# R7FA4M3AF3CFB.net
KiCad netlist of a schematic drawn in Altium Designer
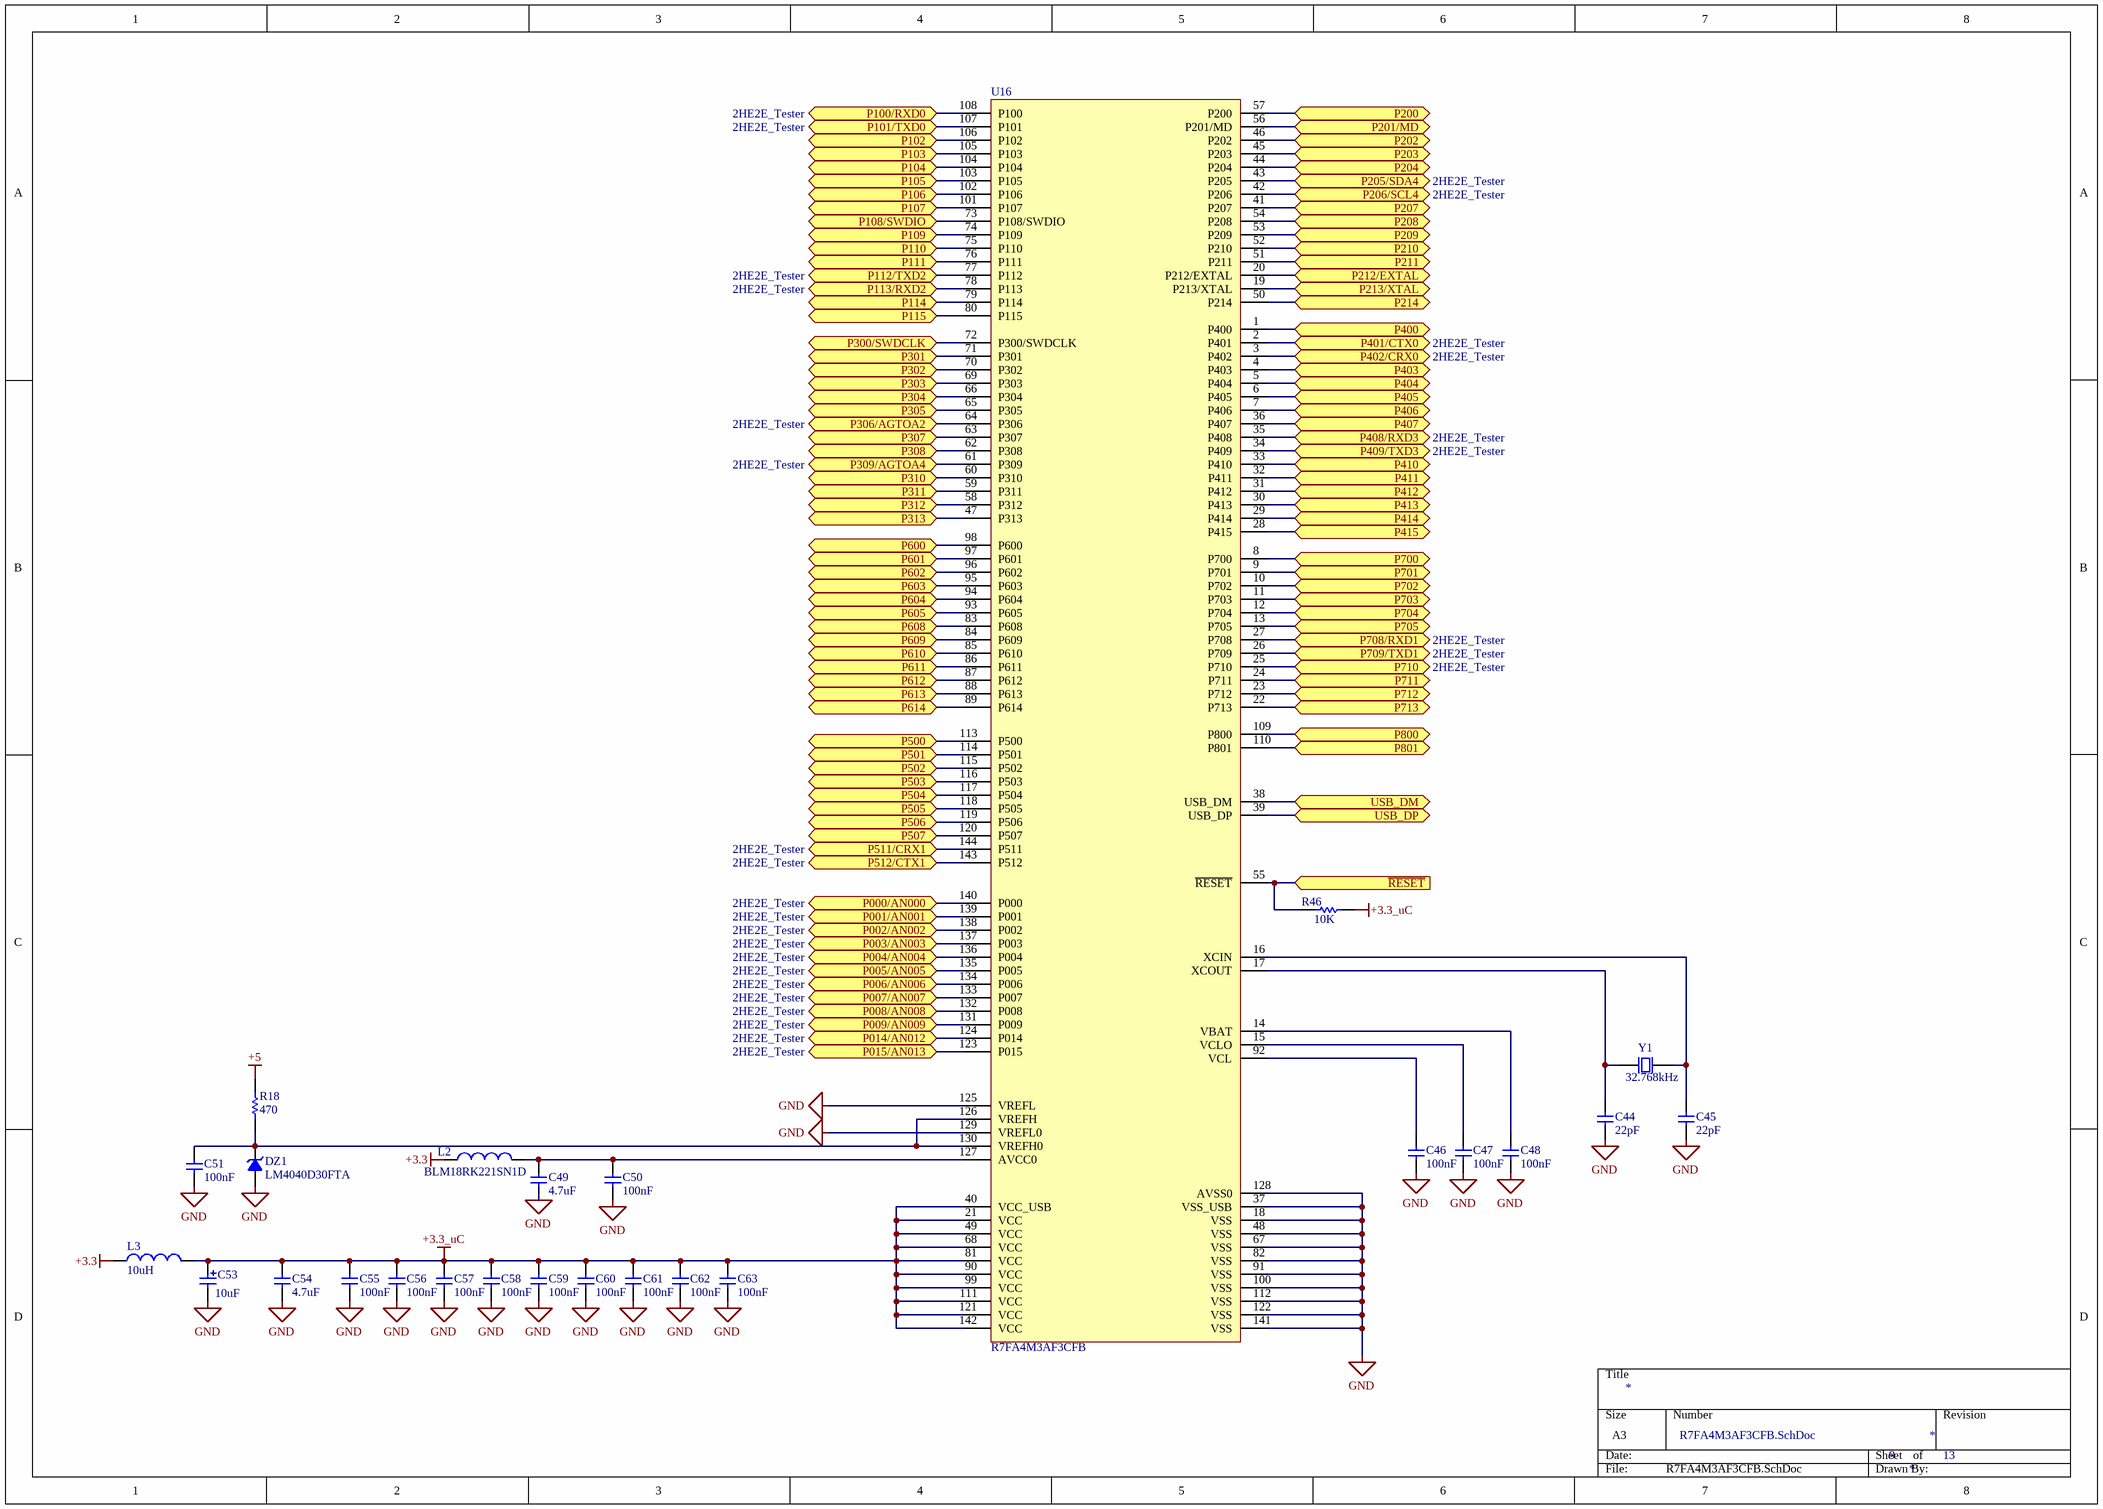
[diagram p0: R7FA4M3AF3CFB.SchDoc]

(export (version "E")
  (design (tool "Eeschema 10.0.6"))
  (components
    (comp (ref "C44")
      (value "22pF")
      (footprint "0603M-C")
      (description "Ceramic Capacitor")
      (fields (field (name "Comment") "Cap Ceramic"))
      (libsource (lib "Plume") (part "Cap Ceramic"))
    )
    (comp (ref "C45")
      (value "22pF")
      (footprint "0603M-C")
      (description "Ceramic Capacitor")
      (fields (field (name "Comment") "Cap Ceramic"))
      (libsource (lib "Plume") (part "Cap Ceramic"))
    )
    (comp (ref "C46")
      (value "100nF")
      (footprint "0603M-C")
      (description "Ceramic Capacitor 25V")
      (fields (field (name "Comment") "Cap Ceramic"))
      (libsource (lib "Plume") (part "Cap Ceramic"))
    )
    (comp (ref "C47")
      (value "100nF")
      (footprint "0603M-C")
      (description "Ceramic Capacitor 25V")
      (fields (field (name "Comment") "Cap Ceramic"))
      (libsource (lib "Plume") (part "Cap Ceramic"))
    )
    (comp (ref "C48")
      (value "100nF")
      (footprint "0603M-C")
      (description "Ceramic Capacitor 25V")
      (fields (field (name "Comment") "Cap Ceramic"))
      (libsource (lib "Plume") (part "Cap Ceramic"))
    )
    (comp (ref "C49")
      (value "4.7uF")
      (footprint "0603M-C")
      (description "Ceramic Capacitor 6.3V")
      (fields (field (name "Comment") "Cap Ceramic"))
      (libsource (lib "Plume") (part "Cap Ceramic"))
    )
    (comp (ref "C50")
      (value "100nF")
      (footprint "0603M-C")
      (description "Ceramic Capacitor 25V")
      (fields (field (name "Comment") "Cap Ceramic"))
      (libsource (lib "Plume") (part "Cap Ceramic"))
    )
    (comp (ref "C51")
      (value "100nF")
      (footprint "0603M-C")
      (description "Ceramic Capacitor 25V")
      (fields (field (name "Comment") "Cap Ceramic"))
      (libsource (lib "Plume") (part "Cap Ceramic"))
    )
    (comp (ref "C53")
      (value "10uF")
      (footprint "Cap CASE A")
      (description "Capacitor tantalio 10V")
      (fields (field (name "Comment") "Cap Tantalio"))
      (libsource (lib "Plume") (part "Cap Tantalio"))
    )
    (comp (ref "C54")
      (value "4.7uF")
      (footprint "0603M-C")
      (description "Ceramic Capacitor 6.3V")
      (fields (field (name "Comment") "Cap Ceramic"))
      (libsource (lib "Plume") (part "Cap Ceramic"))
    )
    (comp (ref "C55")
      (value "100nF")
      (footprint "0603M-C")
      (description "Ceramic Capacitor 25V")
      (fields (field (name "Comment") "Cap Ceramic"))
      (libsource (lib "Plume") (part "Cap Ceramic"))
    )
    (comp (ref "C56")
      (value "100nF")
      (footprint "0603M-C")
      (description "Ceramic Capacitor 25V")
      (fields (field (name "Comment") "Cap Ceramic"))
      (libsource (lib "Plume") (part "Cap Ceramic"))
    )
    (comp (ref "C57")
      (value "100nF")
      (footprint "0603M-C")
      (description "Ceramic Capacitor 25V")
      (fields (field (name "Comment") "Cap Ceramic"))
      (libsource (lib "Plume") (part "Cap Ceramic"))
    )
    (comp (ref "C58")
      (value "100nF")
      (footprint "0603M-C")
      (description "Ceramic Capacitor 25V")
      (fields (field (name "Comment") "Cap Ceramic"))
      (libsource (lib "Plume") (part "Cap Ceramic"))
    )
    (comp (ref "C59")
      (value "100nF")
      (footprint "0603M-C")
      (description "Ceramic Capacitor 25V")
      (fields (field (name "Comment") "Cap Ceramic"))
      (libsource (lib "Plume") (part "Cap Ceramic"))
    )
    (comp (ref "C60")
      (value "100nF")
      (footprint "0603M-C")
      (description "Ceramic Capacitor 25V")
      (fields (field (name "Comment") "Cap Ceramic"))
      (libsource (lib "Plume") (part "Cap Ceramic"))
    )
    (comp (ref "C61")
      (value "100nF")
      (footprint "0603M-C")
      (description "Ceramic Capacitor 25V")
      (fields (field (name "Comment") "Cap Ceramic"))
      (libsource (lib "Plume") (part "Cap Ceramic"))
    )
    (comp (ref "C62")
      (value "100nF")
      (footprint "0603M-C")
      (description "Ceramic Capacitor 25V")
      (fields (field (name "Comment") "Cap Ceramic"))
      (libsource (lib "Plume") (part "Cap Ceramic"))
    )
    (comp (ref "C63")
      (value "100nF")
      (footprint "0603M-C")
      (description "Ceramic Capacitor 25V")
      (fields (field (name "Comment") "Cap Ceramic"))
      (libsource (lib "Plume") (part "Cap Ceramic"))
    )
    (comp (ref "DZ1")
      (value "LM4040D30FTA")
      (footprint "SOT23 ZR4040")
      (description "Reference 3V")
      (libsource (lib "Plume") (part "Diodo Zener"))
    )
    (comp (ref "L2")
      (value "BLM18RK221SN1D")
      (footprint "0603M")
      (description "Ferrite Bead")
      (libsource (lib "Plume") (part "Induttanza"))
    )
    (comp (ref "L3")
      (value "10uH")
      (footprint "1210ML")
      (description "WE 744032100")
      (fields (field (name "Comment") "Induttanza"))
      (libsource (lib "Plume") (part "Induttanza"))
    )
    (comp (ref "R18")
      (value "470")
      (footprint "0603M")
      (description "Resistor")
      (libsource (lib "Plume") (part "Resistor"))
    )
    (comp (ref "R46")
      (value "10K")
      (footprint "0603M")
      (description "Resistor")
      (libsource (lib "Plume") (part "Resistor"))
    )
    (comp (ref "U16")
      (value "R7FA4M3AF3CFB")
      (footprint "TQFP50P2200X2200X170-144N")
      (description "RA4M3 100 MHz Arm Cortex-M33 core 144 pin")
      (libsource (lib "Plume") (part "R7FA4M3Ax3CFB"))
    )
    (comp (ref "Y1")
      (value "32.768kHz")
      (footprint "WE-XTAL_CFPX-217")
      (description "WE-XTAL  830108488401- Watch Crystals  32.768kHz ±20ppm 12.5pF")
      (libsource (lib "Plume") (part "Quarzo"))
    )
  )
  (nets
    (net (code "1") (name "+3.3") (class "Default")
      (node (ref "L2") (pin "1") (pinfunction "1_1") (pintype "passive"))
      (node (ref "L3") (pin "1") (pinfunction "1_1") (pintype "passive"))
    )
    (net (code "2") (name "+3.3_uC") (class "Default")
      (node (ref "C53") (pin "1") (pinfunction "1_1") (pintype "passive"))
      (node (ref "C54") (pin "2") (pinfunction "2_2") (pintype "passive"))
      (node (ref "C55") (pin "2") (pinfunction "2_2") (pintype "passive"))
      (node (ref "C56") (pin "2") (pinfunction "2_2") (pintype "passive"))
      (node (ref "C57") (pin "2") (pinfunction "2_2") (pintype "passive"))
      (node (ref "C58") (pin "2") (pinfunction "2_2") (pintype "passive"))
      (node (ref "C59") (pin "2") (pinfunction "2_2") (pintype "passive"))
      (node (ref "C60") (pin "2") (pinfunction "2_2") (pintype "passive"))
      (node (ref "C61") (pin "2") (pinfunction "2_2") (pintype "passive"))
      (node (ref "C62") (pin "2") (pinfunction "2_2") (pintype "passive"))
      (node (ref "C63") (pin "2") (pinfunction "2_2") (pintype "passive"))
      (node (ref "L3") (pin "2") (pinfunction "2_2") (pintype "passive"))
      (node (ref "R46") (pin "1") (pinfunction "1_1") (pintype "passive"))
      (node (ref "U16") (pin "111") (pinfunction "VCC_111") (pintype "passive"))
      (node (ref "U16") (pin "121") (pinfunction "VCC_121") (pintype "passive"))
      (node (ref "U16") (pin "142") (pinfunction "VCC_142") (pintype "passive"))
      (node (ref "U16") (pin "21") (pinfunction "VCC_21") (pintype "passive"))
      (node (ref "U16") (pin "40") (pinfunction "VCC_USB_40") (pintype "passive"))
      (node (ref "U16") (pin "49") (pinfunction "VCC_49") (pintype "passive"))
      (node (ref "U16") (pin "68") (pinfunction "VCC_68") (pintype "passive"))
      (node (ref "U16") (pin "81") (pinfunction "VCC_81") (pintype "passive"))
      (node (ref "U16") (pin "90") (pinfunction "VCC_90") (pintype "passive"))
      (node (ref "U16") (pin "99") (pinfunction "VCC_99") (pintype "passive"))
    )
    (net (code "3") (name "+5") (class "Default")
      (node (ref "R18") (pin "2") (pinfunction "2_2") (pintype "passive"))
    )
    (net (code "4") (name "/P000{slash}AN000") (class "Default")
      (node (ref "U16") (pin "140") (pinfunction "P000_140") (pintype "passive"))
    )
    (net (code "5") (name "/P001{slash}AN001") (class "Default")
      (node (ref "U16") (pin "139") (pinfunction "P001_139") (pintype "passive"))
    )
    (net (code "6") (name "/P002{slash}AN002") (class "Default")
      (node (ref "U16") (pin "138") (pinfunction "P002_138") (pintype "passive"))
    )
    (net (code "7") (name "/P003{slash}AN003") (class "Default")
      (node (ref "U16") (pin "137") (pinfunction "P003_137") (pintype "passive"))
    )
    (net (code "8") (name "/P004{slash}AN004") (class "Default")
      (node (ref "U16") (pin "136") (pinfunction "P004_136") (pintype "passive"))
    )
    (net (code "9") (name "/P005{slash}AN005") (class "Default")
      (node (ref "U16") (pin "135") (pinfunction "P005_135") (pintype "passive"))
    )
    (net (code "10") (name "/P006{slash}AN006") (class "Default")
      (node (ref "U16") (pin "134") (pinfunction "P006_134") (pintype "passive"))
    )
    (net (code "11") (name "/P007{slash}AN007") (class "Default")
      (node (ref "U16") (pin "133") (pinfunction "P007_133") (pintype "passive"))
    )
    (net (code "12") (name "/P008{slash}AN008") (class "Default")
      (node (ref "U16") (pin "132") (pinfunction "P008_132") (pintype "passive"))
    )
    (net (code "13") (name "/P009{slash}AN009") (class "Default")
      (node (ref "U16") (pin "131") (pinfunction "P009_131") (pintype "passive"))
    )
    (net (code "14") (name "/P014{slash}AN012") (class "Default")
      (node (ref "U16") (pin "124") (pinfunction "P014_124") (pintype "passive"))
    )
    (net (code "15") (name "/P015{slash}AN013") (class "Default")
      (node (ref "U16") (pin "123") (pinfunction "P015_123") (pintype "passive"))
    )
    (net (code "16") (name "/P100{slash}RXD0") (class "Default")
      (node (ref "U16") (pin "108") (pinfunction "P100_108") (pintype "passive"))
    )
    (net (code "17") (name "/P101{slash}TXD0") (class "Default")
      (node (ref "U16") (pin "107") (pinfunction "P101_107") (pintype "passive"))
    )
    (net (code "18") (name "/P102") (class "Default")
      (node (ref "U16") (pin "106") (pinfunction "P102_106") (pintype "passive"))
    )
    (net (code "19") (name "/P103") (class "Default")
      (node (ref "U16") (pin "105") (pinfunction "P103_105") (pintype "passive"))
    )
    (net (code "20") (name "/P104") (class "Default")
      (node (ref "U16") (pin "104") (pinfunction "P104_104") (pintype "passive"))
    )
    (net (code "21") (name "/P105") (class "Default")
      (node (ref "U16") (pin "103") (pinfunction "P105_103") (pintype "passive"))
    )
    (net (code "22") (name "/P106") (class "Default")
      (node (ref "U16") (pin "102") (pinfunction "P106_102") (pintype "passive"))
    )
    (net (code "23") (name "/P107") (class "Default")
      (node (ref "U16") (pin "101") (pinfunction "P107_101") (pintype "passive"))
    )
    (net (code "24") (name "/P108{slash}SWDIO") (class "Default")
      (node (ref "U16") (pin "73") (pinfunction "P108/SWDIO_73") (pintype "passive"))
    )
    (net (code "25") (name "/P109") (class "Default")
      (node (ref "U16") (pin "74") (pinfunction "P109_74") (pintype "passive"))
    )
    (net (code "26") (name "/P110") (class "Default")
      (node (ref "U16") (pin "75") (pinfunction "P110_75") (pintype "passive"))
    )
    (net (code "27") (name "/P111") (class "Default")
      (node (ref "U16") (pin "76") (pinfunction "P111_76") (pintype "passive"))
    )
    (net (code "28") (name "/P112{slash}TXD2") (class "Default")
      (node (ref "U16") (pin "77") (pinfunction "P112_77") (pintype "passive"))
    )
    (net (code "29") (name "/P113{slash}RXD2") (class "Default")
      (node (ref "U16") (pin "78") (pinfunction "P113_78") (pintype "passive"))
    )
    (net (code "30") (name "/P114") (class "Default")
      (node (ref "U16") (pin "79") (pinfunction "P114_79") (pintype "passive"))
    )
    (net (code "31") (name "/P115") (class "Default")
      (node (ref "U16") (pin "80") (pinfunction "P115_80") (pintype "passive"))
    )
    (net (code "32") (name "/P200") (class "Default")
      (node (ref "U16") (pin "57") (pinfunction "P200_57") (pintype "passive"))
    )
    (net (code "33") (name "/P201{slash}MD") (class "Default")
      (node (ref "U16") (pin "56") (pinfunction "P201/MD_56") (pintype "passive"))
    )
    (net (code "34") (name "/P202") (class "Default")
      (node (ref "U16") (pin "46") (pinfunction "P202_46") (pintype "passive"))
    )
    (net (code "35") (name "/P203") (class "Default")
      (node (ref "U16") (pin "45") (pinfunction "P203_45") (pintype "passive"))
    )
    (net (code "36") (name "/P204") (class "Default")
      (node (ref "U16") (pin "44") (pinfunction "P204_44") (pintype "passive"))
    )
    (net (code "37") (name "/P205{slash}SDA4") (class "Default")
      (node (ref "U16") (pin "43") (pinfunction "P205_43") (pintype "passive"))
    )
    (net (code "38") (name "/P206{slash}SCL4") (class "Default")
      (node (ref "U16") (pin "42") (pinfunction "P206_42") (pintype "passive"))
    )
    (net (code "39") (name "/P207") (class "Default")
      (node (ref "U16") (pin "41") (pinfunction "P207_41") (pintype "passive"))
    )
    (net (code "40") (name "/P208") (class "Default")
      (node (ref "U16") (pin "54") (pinfunction "P208_54") (pintype "passive"))
    )
    (net (code "41") (name "/P209") (class "Default")
      (node (ref "U16") (pin "53") (pinfunction "P209_53") (pintype "passive"))
    )
    (net (code "42") (name "/P210") (class "Default")
      (node (ref "U16") (pin "52") (pinfunction "P210_52") (pintype "passive"))
    )
    (net (code "43") (name "/P211") (class "Default")
      (node (ref "U16") (pin "51") (pinfunction "P211_51") (pintype "passive"))
    )
    (net (code "44") (name "/P212{slash}EXTAL") (class "Default")
      (node (ref "U16") (pin "20") (pinfunction "P212/EXTAL_20") (pintype "passive"))
    )
    (net (code "45") (name "/P213{slash}XTAL") (class "Default")
      (node (ref "U16") (pin "19") (pinfunction "P213/XTAL_19") (pintype "passive"))
    )
    (net (code "46") (name "/P214") (class "Default")
      (node (ref "U16") (pin "50") (pinfunction "P214_50") (pintype "passive"))
    )
    (net (code "47") (name "/P300{slash}SWDCLK") (class "Default")
      (node (ref "U16") (pin "72") (pinfunction "P300/SWDCLK_72") (pintype "passive"))
    )
    (net (code "48") (name "/P301") (class "Default")
      (node (ref "U16") (pin "71") (pinfunction "P301_71") (pintype "passive"))
    )
    (net (code "49") (name "/P302") (class "Default")
      (node (ref "U16") (pin "70") (pinfunction "P302_70") (pintype "passive"))
    )
    (net (code "50") (name "/P303") (class "Default")
      (node (ref "U16") (pin "69") (pinfunction "P303_69") (pintype "passive"))
    )
    (net (code "51") (name "/P304") (class "Default")
      (node (ref "U16") (pin "66") (pinfunction "P304_66") (pintype "passive"))
    )
    (net (code "52") (name "/P305") (class "Default")
      (node (ref "U16") (pin "65") (pinfunction "P305_65") (pintype "passive"))
    )
    (net (code "53") (name "/P306{slash}AGTOA2") (class "Default")
      (node (ref "U16") (pin "64") (pinfunction "P306_64") (pintype "passive"))
    )
    (net (code "54") (name "/P307") (class "Default")
      (node (ref "U16") (pin "63") (pinfunction "P307_63") (pintype "passive"))
    )
    (net (code "55") (name "/P308") (class "Default")
      (node (ref "U16") (pin "62") (pinfunction "P308_62") (pintype "passive"))
    )
    (net (code "56") (name "/P309{slash}AGTOA4") (class "Default")
      (node (ref "U16") (pin "61") (pinfunction "P309_61") (pintype "passive"))
    )
    (net (code "57") (name "/P310") (class "Default")
      (node (ref "U16") (pin "60") (pinfunction "P310_60") (pintype "passive"))
    )
    (net (code "58") (name "/P311") (class "Default")
      (node (ref "U16") (pin "59") (pinfunction "P311_59") (pintype "passive"))
    )
    (net (code "59") (name "/P312") (class "Default")
      (node (ref "U16") (pin "58") (pinfunction "P312_58") (pintype "passive"))
    )
    (net (code "60") (name "/P313") (class "Default")
      (node (ref "U16") (pin "47") (pinfunction "P313_47") (pintype "passive"))
    )
    (net (code "61") (name "/P400") (class "Default")
      (node (ref "U16") (pin "1") (pinfunction "P400_1") (pintype "passive"))
    )
    (net (code "62") (name "/P401{slash}CTX0") (class "Default")
      (node (ref "U16") (pin "2") (pinfunction "P401_2") (pintype "passive"))
    )
    (net (code "63") (name "/P402{slash}CRX0") (class "Default")
      (node (ref "U16") (pin "3") (pinfunction "P402_3") (pintype "passive"))
    )
    (net (code "64") (name "/P403") (class "Default")
      (node (ref "U16") (pin "4") (pinfunction "P403_4") (pintype "passive"))
    )
    (net (code "65") (name "/P404") (class "Default")
      (node (ref "U16") (pin "5") (pinfunction "P404_5") (pintype "passive"))
    )
    (net (code "66") (name "/P405") (class "Default")
      (node (ref "U16") (pin "6") (pinfunction "P405_6") (pintype "passive"))
    )
    (net (code "67") (name "/P406") (class "Default")
      (node (ref "U16") (pin "7") (pinfunction "P406_7") (pintype "passive"))
    )
    (net (code "68") (name "/P407") (class "Default")
      (node (ref "U16") (pin "36") (pinfunction "P407_36") (pintype "passive"))
    )
    (net (code "69") (name "/P408{slash}RXD3") (class "Default")
      (node (ref "U16") (pin "35") (pinfunction "P408_35") (pintype "passive"))
    )
    (net (code "70") (name "/P409{slash}TXD3") (class "Default")
      (node (ref "U16") (pin "34") (pinfunction "P409_34") (pintype "passive"))
    )
    (net (code "71") (name "/P410") (class "Default")
      (node (ref "U16") (pin "33") (pinfunction "P410_33") (pintype "passive"))
    )
    (net (code "72") (name "/P411") (class "Default")
      (node (ref "U16") (pin "32") (pinfunction "P411_32") (pintype "passive"))
    )
    (net (code "73") (name "/P412") (class "Default")
      (node (ref "U16") (pin "31") (pinfunction "P412_31") (pintype "passive"))
    )
    (net (code "74") (name "/P413") (class "Default")
      (node (ref "U16") (pin "30") (pinfunction "P413_30") (pintype "passive"))
    )
    (net (code "75") (name "/P414") (class "Default")
      (node (ref "U16") (pin "29") (pinfunction "P414_29") (pintype "passive"))
    )
    (net (code "76") (name "/P415") (class "Default")
      (node (ref "U16") (pin "28") (pinfunction "P415_28") (pintype "passive"))
    )
    (net (code "77") (name "/P500") (class "Default")
      (node (ref "U16") (pin "113") (pinfunction "P500_113") (pintype "passive"))
    )
    (net (code "78") (name "/P501") (class "Default")
      (node (ref "U16") (pin "114") (pinfunction "P501_114") (pintype "passive"))
    )
    (net (code "79") (name "/P502") (class "Default")
      (node (ref "U16") (pin "115") (pinfunction "P502_115") (pintype "passive"))
    )
    (net (code "80") (name "/P503") (class "Default")
      (node (ref "U16") (pin "116") (pinfunction "P503_116") (pintype "passive"))
    )
    (net (code "81") (name "/P504") (class "Default")
      (node (ref "U16") (pin "117") (pinfunction "P504_117") (pintype "passive"))
    )
    (net (code "82") (name "/P505") (class "Default")
      (node (ref "U16") (pin "118") (pinfunction "P505_118") (pintype "passive"))
    )
    (net (code "83") (name "/P506") (class "Default")
      (node (ref "U16") (pin "119") (pinfunction "P506_119") (pintype "passive"))
    )
    (net (code "84") (name "/P507") (class "Default")
      (node (ref "U16") (pin "120") (pinfunction "P507_120") (pintype "passive"))
    )
    (net (code "85") (name "/P511{slash}CRX1") (class "Default")
      (node (ref "U16") (pin "144") (pinfunction "P511_144") (pintype "passive"))
    )
    (net (code "86") (name "/P512{slash}CTX1") (class "Default")
      (node (ref "U16") (pin "143") (pinfunction "P512_143") (pintype "passive"))
    )
    (net (code "87") (name "/P600") (class "Default")
      (node (ref "U16") (pin "98") (pinfunction "P600_98") (pintype "passive"))
    )
    (net (code "88") (name "/P601") (class "Default")
      (node (ref "U16") (pin "97") (pinfunction "P601_97") (pintype "passive"))
    )
    (net (code "89") (name "/P602") (class "Default")
      (node (ref "U16") (pin "96") (pinfunction "P602_96") (pintype "passive"))
    )
    (net (code "90") (name "/P603") (class "Default")
      (node (ref "U16") (pin "95") (pinfunction "P603_95") (pintype "passive"))
    )
    (net (code "91") (name "/P604") (class "Default")
      (node (ref "U16") (pin "94") (pinfunction "P604_94") (pintype "passive"))
    )
    (net (code "92") (name "/P605") (class "Default")
      (node (ref "U16") (pin "93") (pinfunction "P605_93") (pintype "passive"))
    )
    (net (code "93") (name "/P608") (class "Default")
      (node (ref "U16") (pin "83") (pinfunction "P608_83") (pintype "passive"))
    )
    (net (code "94") (name "/P609") (class "Default")
      (node (ref "U16") (pin "84") (pinfunction "P609_84") (pintype "passive"))
    )
    (net (code "95") (name "/P610") (class "Default")
      (node (ref "U16") (pin "85") (pinfunction "P610_85") (pintype "passive"))
    )
    (net (code "96") (name "/P611") (class "Default")
      (node (ref "U16") (pin "86") (pinfunction "P611_86") (pintype "passive"))
    )
    (net (code "97") (name "/P612") (class "Default")
      (node (ref "U16") (pin "87") (pinfunction "P612_87") (pintype "passive"))
    )
    (net (code "98") (name "/P613") (class "Default")
      (node (ref "U16") (pin "88") (pinfunction "P613_88") (pintype "passive"))
    )
    (net (code "99") (name "/P614") (class "Default")
      (node (ref "U16") (pin "89") (pinfunction "P614_89") (pintype "passive"))
    )
    (net (code "100") (name "/P700") (class "Default")
      (node (ref "U16") (pin "8") (pinfunction "P700_8") (pintype "passive"))
    )
    (net (code "101") (name "/P701") (class "Default")
      (node (ref "U16") (pin "9") (pinfunction "P701_9") (pintype "passive"))
    )
    (net (code "102") (name "/P702") (class "Default")
      (node (ref "U16") (pin "10") (pinfunction "P702_10") (pintype "passive"))
    )
    (net (code "103") (name "/P703") (class "Default")
      (node (ref "U16") (pin "11") (pinfunction "P703_11") (pintype "passive"))
    )
    (net (code "104") (name "/P704") (class "Default")
      (node (ref "U16") (pin "12") (pinfunction "P704_12") (pintype "passive"))
    )
    (net (code "105") (name "/P705") (class "Default")
      (node (ref "U16") (pin "13") (pinfunction "P705_13") (pintype "passive"))
    )
    (net (code "106") (name "/P708{slash}RXD1") (class "Default")
      (node (ref "U16") (pin "27") (pinfunction "P708_27") (pintype "passive"))
    )
    (net (code "107") (name "/P709{slash}TXD1") (class "Default")
      (node (ref "U16") (pin "26") (pinfunction "P709_26") (pintype "passive"))
    )
    (net (code "108") (name "/P710") (class "Default")
      (node (ref "U16") (pin "25") (pinfunction "P710_25") (pintype "passive"))
    )
    (net (code "109") (name "/P711") (class "Default")
      (node (ref "U16") (pin "24") (pinfunction "P711_24") (pintype "passive"))
    )
    (net (code "110") (name "/P712") (class "Default")
      (node (ref "U16") (pin "23") (pinfunction "P712_23") (pintype "passive"))
    )
    (net (code "111") (name "/P713") (class "Default")
      (node (ref "U16") (pin "22") (pinfunction "P713_22") (pintype "passive"))
    )
    (net (code "112") (name "/P800") (class "Default")
      (node (ref "U16") (pin "109") (pinfunction "P800_109") (pintype "passive"))
    )
    (net (code "113") (name "/P801") (class "Default")
      (node (ref "U16") (pin "110") (pinfunction "P801_110") (pintype "passive"))
    )
    (net (code "114") (name "/USB_DM") (class "Default")
      (node (ref "U16") (pin "38") (pinfunction "USB_DM_38") (pintype "passive"))
    )
    (net (code "115") (name "/USB_DP") (class "Default")
      (node (ref "U16") (pin "39") (pinfunction "USB_DP_39") (pintype "passive"))
    )
    (net (code "116") (name "/~{RESET}") (class "Default")
      (node (ref "R46") (pin "2") (pinfunction "2_2") (pintype "passive"))
      (node (ref "U16") (pin "55") (pinfunction "~{RESET}_55") (pintype "passive"))
    )
    (net (code "117") (name "GND") (class "Default")
      (node (ref "C44") (pin "1") (pinfunction "1_1") (pintype "passive"))
      (node (ref "C45") (pin "1") (pinfunction "1_1") (pintype "passive"))
      (node (ref "C46") (pin "1") (pinfunction "1_1") (pintype "passive"))
      (node (ref "C47") (pin "1") (pinfunction "1_1") (pintype "passive"))
      (node (ref "C48") (pin "1") (pinfunction "1_1") (pintype "passive"))
      (node (ref "C49") (pin "1") (pinfunction "1_1") (pintype "passive"))
      (node (ref "C50") (pin "1") (pinfunction "1_1") (pintype "passive"))
      (node (ref "C51") (pin "1") (pinfunction "1_1") (pintype "passive"))
      (node (ref "C53") (pin "2") (pinfunction "2_2") (pintype "passive"))
      (node (ref "C54") (pin "1") (pinfunction "1_1") (pintype "passive"))
      (node (ref "C55") (pin "1") (pinfunction "1_1") (pintype "passive"))
      (node (ref "C56") (pin "1") (pinfunction "1_1") (pintype "passive"))
      (node (ref "C57") (pin "1") (pinfunction "1_1") (pintype "passive"))
      (node (ref "C58") (pin "1") (pinfunction "1_1") (pintype "passive"))
      (node (ref "C59") (pin "1") (pinfunction "1_1") (pintype "passive"))
      (node (ref "C60") (pin "1") (pinfunction "1_1") (pintype "passive"))
      (node (ref "C61") (pin "1") (pinfunction "1_1") (pintype "passive"))
      (node (ref "C62") (pin "1") (pinfunction "1_1") (pintype "passive"))
      (node (ref "C63") (pin "1") (pinfunction "1_1") (pintype "passive"))
      (node (ref "DZ1") (pin "1") (pinfunction "A_1") (pintype "passive"))
      (node (ref "U16") (pin "100") (pinfunction "VSS_100") (pintype "passive"))
      (node (ref "U16") (pin "112") (pinfunction "VSS_112") (pintype "passive"))
      (node (ref "U16") (pin "122") (pinfunction "VSS_122") (pintype "passive"))
      (node (ref "U16") (pin "125") (pinfunction "VREFL_125") (pintype "passive"))
      (node (ref "U16") (pin "128") (pinfunction "AVSS0_128") (pintype "passive"))
      (node (ref "U16") (pin "129") (pinfunction "VREFL0_129") (pintype "passive"))
      (node (ref "U16") (pin "141") (pinfunction "VSS_141") (pintype "passive"))
      (node (ref "U16") (pin "18") (pinfunction "VSS_18") (pintype "passive"))
      (node (ref "U16") (pin "37") (pinfunction "VSS_USB_37") (pintype "passive"))
      (node (ref "U16") (pin "48") (pinfunction "VSS_48") (pintype "passive"))
      (node (ref "U16") (pin "67") (pinfunction "VSS_67") (pintype "passive"))
      (node (ref "U16") (pin "82") (pinfunction "VSS_82") (pintype "passive"))
      (node (ref "U16") (pin "91") (pinfunction "VSS_91") (pintype "passive"))
    )
    (net (code "118") (name "Net-(DZ1-K)") (class "Default")
      (node (ref "C51") (pin "2") (pinfunction "2_2") (pintype "passive"))
      (node (ref "DZ1") (pin "2") (pinfunction "K_2") (pintype "passive"))
      (node (ref "R18") (pin "1") (pinfunction "1_1") (pintype "passive"))
      (node (ref "U16") (pin "126") (pinfunction "VREFH_126") (pintype "passive"))
      (node (ref "U16") (pin "130") (pinfunction "VREFH0_130") (pintype "passive"))
    )
    (net (code "119") (name "Net-(U16-AVCC0)") (class "Default")
      (node (ref "C49") (pin "2") (pinfunction "2_2") (pintype "passive"))
      (node (ref "C50") (pin "2") (pinfunction "2_2") (pintype "passive"))
      (node (ref "L2") (pin "2") (pinfunction "2_2") (pintype "passive"))
      (node (ref "U16") (pin "127") (pinfunction "AVCC0_127") (pintype "passive"))
    )
    (net (code "120") (name "Net-(U16-VBAT)") (class "Default")
      (node (ref "C48") (pin "2") (pinfunction "2_2") (pintype "passive"))
      (node (ref "U16") (pin "14") (pinfunction "VBAT_14") (pintype "passive"))
    )
    (net (code "121") (name "Net-(U16-VCL)") (class "Default")
      (node (ref "C46") (pin "2") (pinfunction "2_2") (pintype "passive"))
      (node (ref "U16") (pin "92") (pinfunction "VCL_92") (pintype "passive"))
    )
    (net (code "122") (name "Net-(U16-VCLO)") (class "Default")
      (node (ref "C47") (pin "2") (pinfunction "2_2") (pintype "passive"))
      (node (ref "U16") (pin "15") (pinfunction "VCLO_15") (pintype "passive"))
    )
    (net (code "123") (name "Net-(U16-XCIN)") (class "Default")
      (node (ref "C45") (pin "2") (pinfunction "2_2") (pintype "passive"))
      (node (ref "U16") (pin "16") (pinfunction "XCIN_16") (pintype "passive"))
      (node (ref "Y1") (pin "1") (pinfunction "1_1") (pintype "passive"))
    )
    (net (code "124") (name "Net-(U16-XCOUT)") (class "Default")
      (node (ref "C44") (pin "2") (pinfunction "2_2") (pintype "passive"))
      (node (ref "U16") (pin "17") (pinfunction "XCOUT_17") (pintype "passive"))
      (node (ref "Y1") (pin "2") (pinfunction "2_2") (pintype "passive"))
    )
  )
)
